# Klingel.net
KiCad netlist of a schematic drawn in EasyEDA
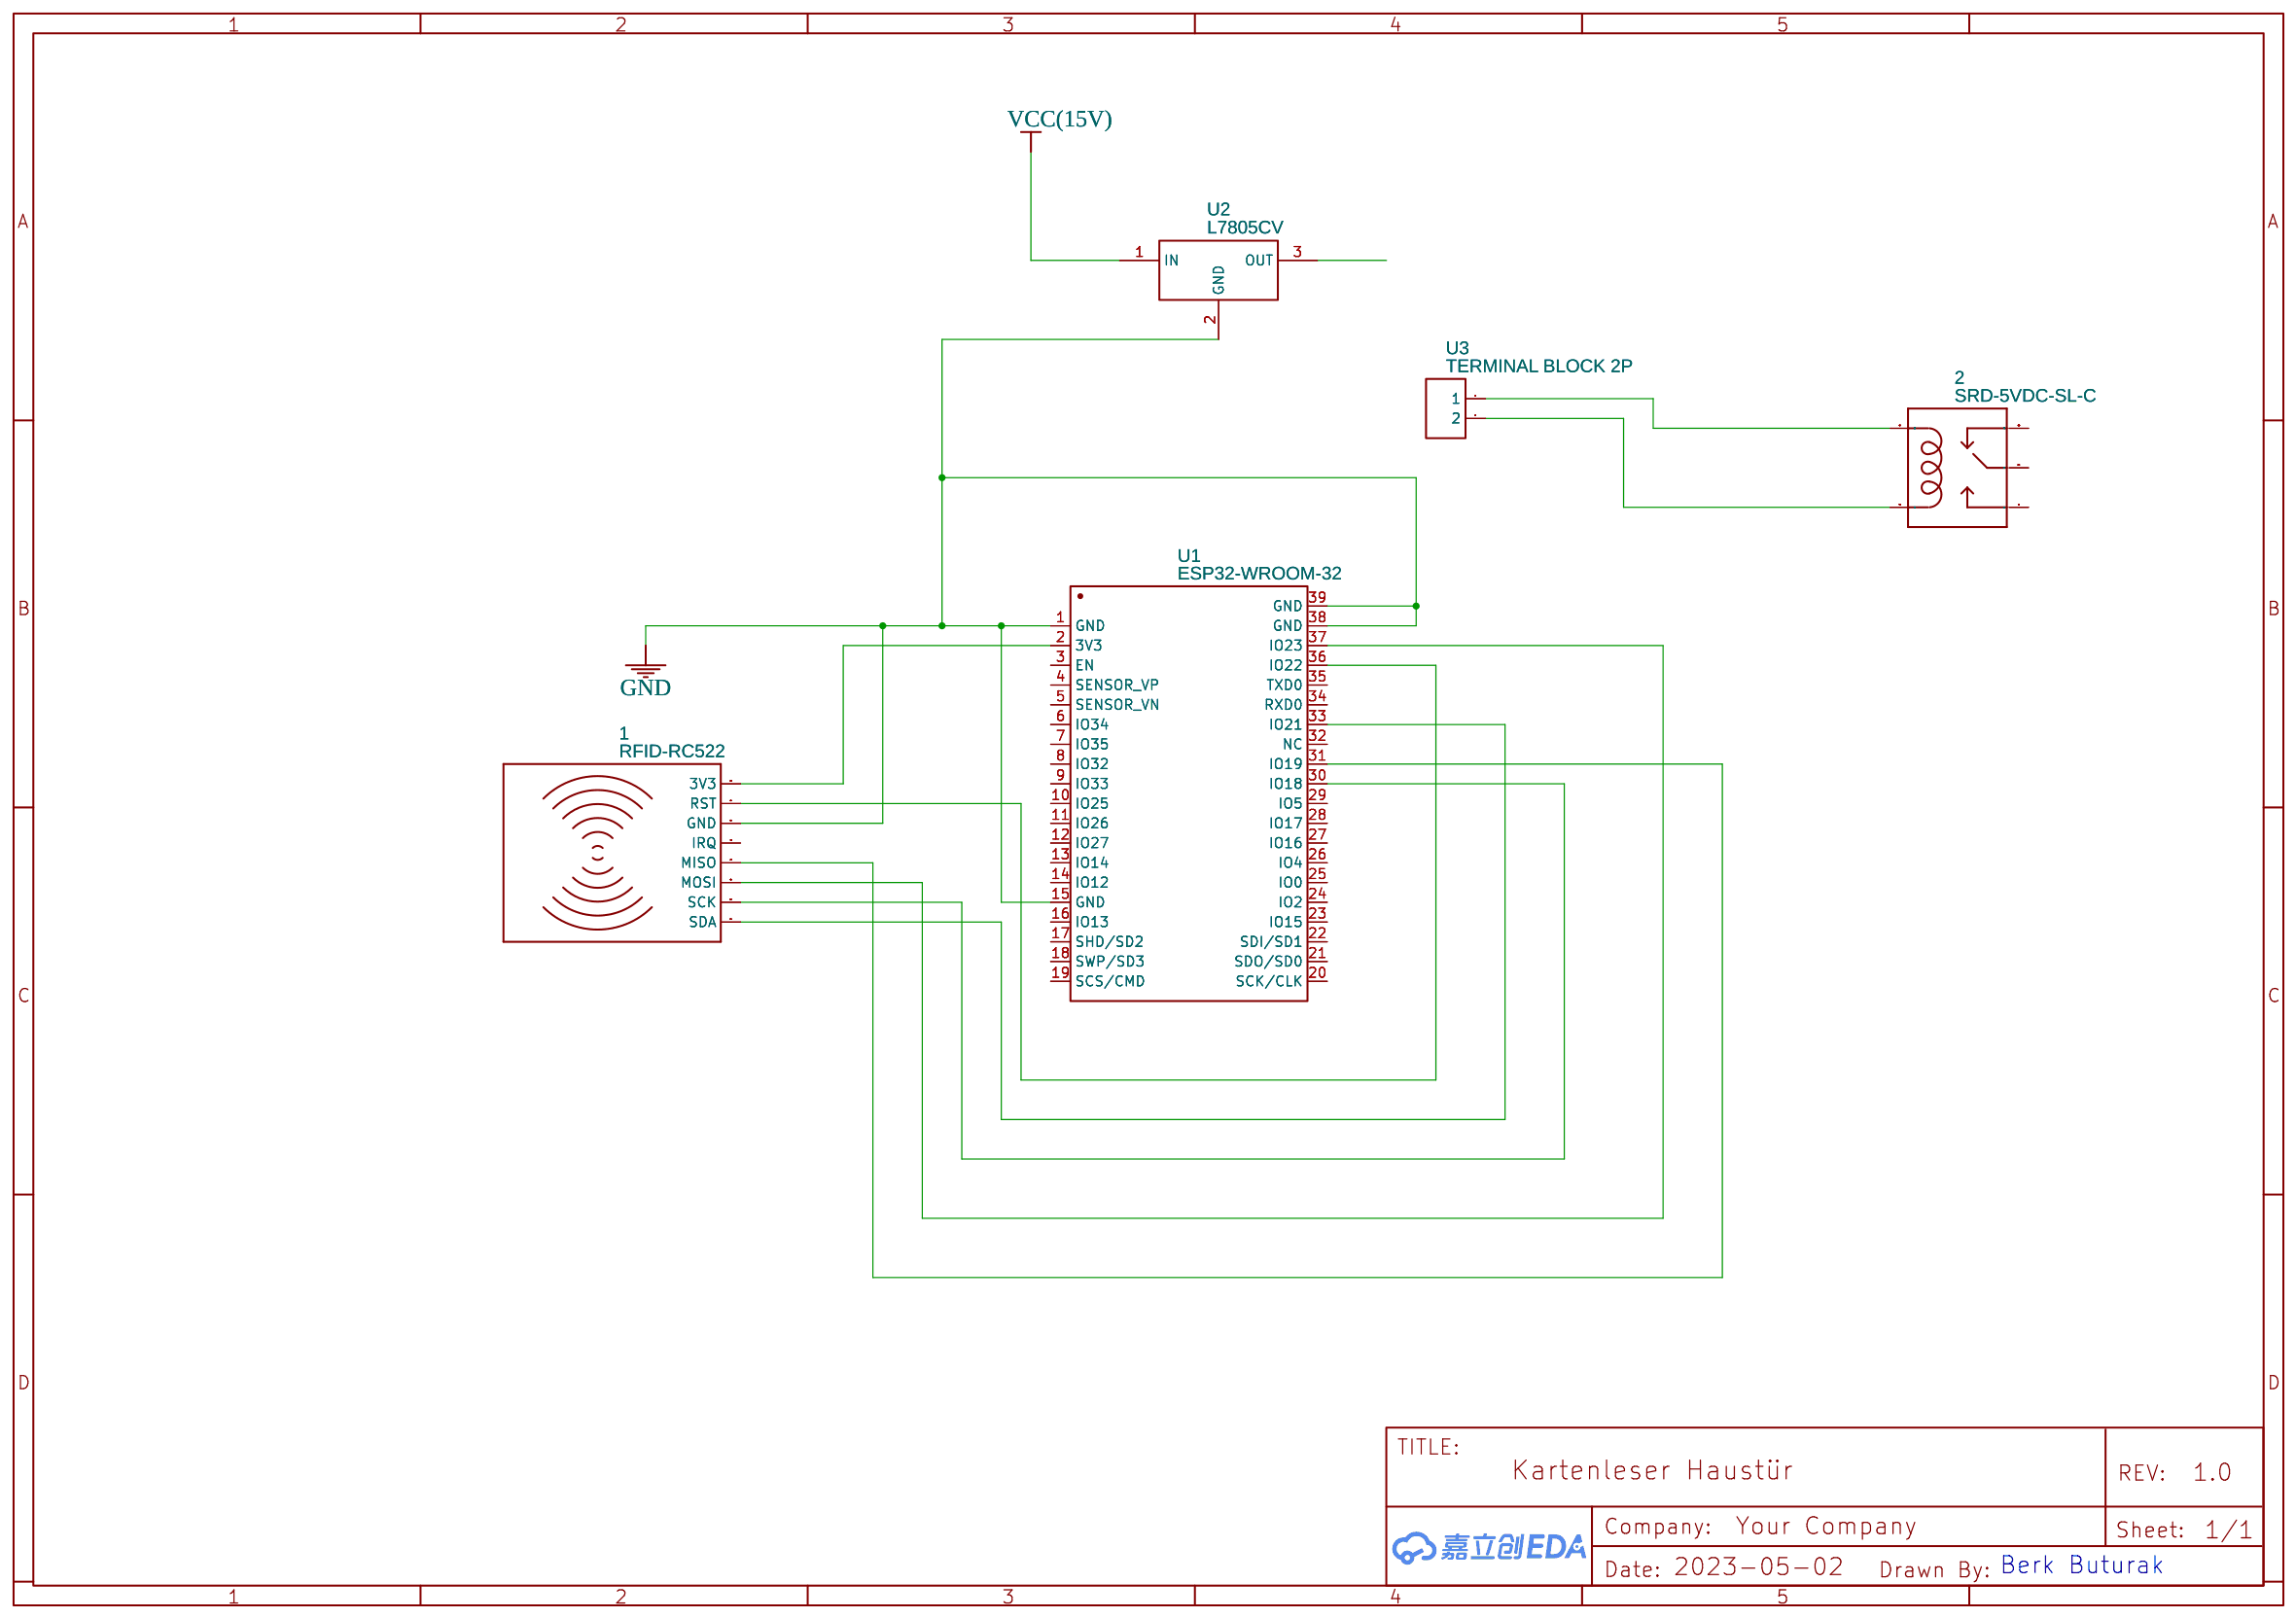
[diagram p0: schematic sheet]

(export (version "E")
  (design (tool "Eeschema 10.0.6"))
  (components
    (comp (ref "1") (value "RFID-RC522") (libsource (lib "") (part "RFID-RC522")))
    (comp (ref "2") (value "SRD-5VDC-SL-C") (libsource (lib "") (part "SRD-5VDC-SL-C")))
    (comp (ref "U1")
      (value "ESP32-WROOM-32")
      (fields
        (field (name "BOM_Manufacturer Part") "ESP32-WROOM-32-N4")
        (field (name "BOM_Supplier Part") "C82899")
      )
      (libsource (lib "") (part "ESP32-WROOM-32"))
    )
    (comp (ref "U2")
      (value "L7805CV")
      (fields (field (name "BOM_Supplier Part") "C111887"))
      (libsource (lib "") (part "L7805CV"))
    )
    (comp (ref "U3") (value "TERMINAL BLOCK 2P") (libsource (lib "") (part "TERMINAL BLOCK 2P")))
  )
  (nets
    (net (code "1") (name "GND") (class "Default")
      (node (ref "1") (pin "GND") (pinfunction "GND_GND") (pintype "bidirectional"))
      (node (ref "U1") (pin "1") (pinfunction "GND_1") (pintype "unspecified"))
      (node (ref "U1") (pin "15") (pinfunction "GND_15") (pintype "unspecified"))
      (node (ref "U1") (pin "38") (pinfunction "GND_38") (pintype "unspecified"))
      (node (ref "U1") (pin "39") (pinfunction "GND_39") (pintype "unspecified"))
      (node (ref "U2") (pin "2") (pinfunction "GND_2") (pintype "passive"))
    )
    (net (code "2") (name "Net-(2-PadCOIL1)") (class "Default")
      (node (ref "2") (pin "COIL1") (pinfunction "COIL1_COIL1") (pintype "bidirectional"))
      (node (ref "U3") (pin "1") (pinfunction "1_1") (pintype "unspecified"))
    )
    (net (code "3") (name "Net-(2-PadCOIL2)") (class "Default")
      (node (ref "2") (pin "COIL2") (pinfunction "COIL2_COIL2") (pintype "bidirectional"))
      (node (ref "U3") (pin "2") (pinfunction "2_2") (pintype "unspecified"))
    )
    (net (code "4") (name "Net-(U1-3V3)") (class "Default")
      (node (ref "1") (pin "3V3") (pinfunction "3V3_3V3") (pintype "bidirectional"))
      (node (ref "U1") (pin "2") (pinfunction "3V3_2") (pintype "unspecified"))
    )
    (net (code "5") (name "Net-(U1-IO18)") (class "Default")
      (node (ref "1") (pin "SCK") (pinfunction "SCK_SCK") (pintype "bidirectional"))
      (node (ref "U1") (pin "30") (pinfunction "IO18_30") (pintype "unspecified"))
    )
    (net (code "6") (name "Net-(U1-IO19)") (class "Default")
      (node (ref "1") (pin "MISO") (pinfunction "MISO_MISO") (pintype "bidirectional"))
      (node (ref "U1") (pin "31") (pinfunction "IO19_31") (pintype "unspecified"))
    )
    (net (code "7") (name "Net-(U1-IO21)") (class "Default")
      (node (ref "1") (pin "SDA") (pinfunction "SDA_SDA") (pintype "bidirectional"))
      (node (ref "U1") (pin "33") (pinfunction "IO21_33") (pintype "unspecified"))
    )
    (net (code "8") (name "Net-(U1-IO22)") (class "Default")
      (node (ref "1") (pin "RST") (pinfunction "RST_RST") (pintype "bidirectional"))
      (node (ref "U1") (pin "36") (pinfunction "IO22_36") (pintype "unspecified"))
    )
    (net (code "9") (name "Net-(U1-IO23)") (class "Default")
      (node (ref "1") (pin "MOSI") (pinfunction "MOSI_MOSI") (pintype "bidirectional"))
      (node (ref "U1") (pin "37") (pinfunction "IO23_37") (pintype "unspecified"))
    )
    (net (code "10") (name "VCC(15V)") (class "Default")
      (node (ref "U2") (pin "1") (pinfunction "IN_1") (pintype "passive"))
    )
    (net (code "11") (name "unconnected-(1-PadIRQ)") (class "Default")
      (node (ref "1") (pin "IRQ") (pinfunction "IRQ_IRQ") (pintype "bidirectional"))
    )
    (net (code "12") (name "unconnected-(2-MAIN-PadCOMMON)") (class "Default")
      (node (ref "2") (pin "COMMON") (pinfunction "MAIN_COMMON") (pintype "bidirectional"))
    )
    (net (code "13") (name "unconnected-(2-NC-PadCLOSED)") (class "Default")
      (node (ref "2") (pin "CLOSED") (pinfunction "NC_CLOSED") (pintype "bidirectional"))
    )
    (net (code "14") (name "unconnected-(2-NO-PadOPEN)") (class "Default")
      (node (ref "2") (pin "OPEN") (pinfunction "NO_OPEN") (pintype "bidirectional"))
    )
    (net (code "15") (name "unconnected-(U1-EN-Pad3)") (class "Default")
      (node (ref "U1") (pin "3") (pinfunction "EN_3") (pintype "unspecified"))
    )
    (net (code "16") (name "unconnected-(U1-IO0-Pad25)") (class "Default")
      (node (ref "U1") (pin "25") (pinfunction "IO0_25") (pintype "unspecified"))
    )
    (net (code "17") (name "unconnected-(U1-IO2-Pad24)") (class "Default")
      (node (ref "U1") (pin "24") (pinfunction "IO2_24") (pintype "unspecified"))
    )
    (net (code "18") (name "unconnected-(U1-IO4-Pad26)") (class "Default")
      (node (ref "U1") (pin "26") (pinfunction "IO4_26") (pintype "unspecified"))
    )
    (net (code "19") (name "unconnected-(U1-IO5-Pad29)") (class "Default")
      (node (ref "U1") (pin "29") (pinfunction "IO5_29") (pintype "unspecified"))
    )
    (net (code "20") (name "unconnected-(U1-IO12-Pad14)") (class "Default")
      (node (ref "U1") (pin "14") (pinfunction "IO12_14") (pintype "unspecified"))
    )
    (net (code "21") (name "unconnected-(U1-IO13-Pad16)") (class "Default")
      (node (ref "U1") (pin "16") (pinfunction "IO13_16") (pintype "unspecified"))
    )
    (net (code "22") (name "unconnected-(U1-IO14-Pad13)") (class "Default")
      (node (ref "U1") (pin "13") (pinfunction "IO14_13") (pintype "unspecified"))
    )
    (net (code "23") (name "unconnected-(U1-IO15-Pad23)") (class "Default")
      (node (ref "U1") (pin "23") (pinfunction "IO15_23") (pintype "unspecified"))
    )
    (net (code "24") (name "unconnected-(U1-IO16-Pad27)") (class "Default")
      (node (ref "U1") (pin "27") (pinfunction "IO16_27") (pintype "unspecified"))
    )
    (net (code "25") (name "unconnected-(U1-IO17-Pad28)") (class "Default")
      (node (ref "U1") (pin "28") (pinfunction "IO17_28") (pintype "unspecified"))
    )
    (net (code "26") (name "unconnected-(U1-IO25-Pad10)") (class "Default")
      (node (ref "U1") (pin "10") (pinfunction "IO25_10") (pintype "unspecified"))
    )
    (net (code "27") (name "unconnected-(U1-IO26-Pad11)") (class "Default")
      (node (ref "U1") (pin "11") (pinfunction "IO26_11") (pintype "unspecified"))
    )
    (net (code "28") (name "unconnected-(U1-IO27-Pad12)") (class "Default")
      (node (ref "U1") (pin "12") (pinfunction "IO27_12") (pintype "unspecified"))
    )
    (net (code "29") (name "unconnected-(U1-IO32-Pad8)") (class "Default")
      (node (ref "U1") (pin "8") (pinfunction "IO32_8") (pintype "unspecified"))
    )
    (net (code "30") (name "unconnected-(U1-IO33-Pad9)") (class "Default")
      (node (ref "U1") (pin "9") (pinfunction "IO33_9") (pintype "unspecified"))
    )
    (net (code "31") (name "unconnected-(U1-IO34-Pad6)") (class "Default")
      (node (ref "U1") (pin "6") (pinfunction "IO34_6") (pintype "unspecified"))
    )
    (net (code "32") (name "unconnected-(U1-IO35-Pad7)") (class "Default")
      (node (ref "U1") (pin "7") (pinfunction "IO35_7") (pintype "unspecified"))
    )
    (net (code "33") (name "unconnected-(U1-NC-Pad32)") (class "Default")
      (node (ref "U1") (pin "32") (pinfunction "NC_32") (pintype "unspecified"))
    )
    (net (code "34") (name "unconnected-(U1-RXD0-Pad34)") (class "Default")
      (node (ref "U1") (pin "34") (pinfunction "RXD0_34") (pintype "unspecified"))
    )
    (net (code "35") (name "unconnected-(U1-SCK{slash}CLK-Pad20)") (class "Default")
      (node (ref "U1") (pin "20") (pinfunction "SCK/CLK_20") (pintype "unspecified"))
    )
    (net (code "36") (name "unconnected-(U1-SCS{slash}CMD-Pad19)") (class "Default")
      (node (ref "U1") (pin "19") (pinfunction "SCS/CMD_19") (pintype "unspecified"))
    )
    (net (code "37") (name "unconnected-(U1-SDI{slash}SD1-Pad22)") (class "Default")
      (node (ref "U1") (pin "22") (pinfunction "SDI/SD1_22") (pintype "unspecified"))
    )
    (net (code "38") (name "unconnected-(U1-SDO{slash}SD0-Pad21)") (class "Default")
      (node (ref "U1") (pin "21") (pinfunction "SDO/SD0_21") (pintype "unspecified"))
    )
    (net (code "39") (name "unconnected-(U1-SENSOR_VN-Pad5)") (class "Default")
      (node (ref "U1") (pin "5") (pinfunction "SENSOR_VN_5") (pintype "unspecified"))
    )
    (net (code "40") (name "unconnected-(U1-SENSOR_VP-Pad4)") (class "Default")
      (node (ref "U1") (pin "4") (pinfunction "SENSOR_VP_4") (pintype "unspecified"))
    )
    (net (code "41") (name "unconnected-(U1-SHD{slash}SD2-Pad17)") (class "Default")
      (node (ref "U1") (pin "17") (pinfunction "SHD/SD2_17") (pintype "unspecified"))
    )
    (net (code "42") (name "unconnected-(U1-SWP{slash}SD3-Pad18)") (class "Default")
      (node (ref "U1") (pin "18") (pinfunction "SWP/SD3_18") (pintype "unspecified"))
    )
    (net (code "43") (name "unconnected-(U1-TXD0-Pad35)") (class "Default")
      (node (ref "U1") (pin "35") (pinfunction "TXD0_35") (pintype "unspecified"))
    )
    (net (code "44") (name "unconnected-(U2-OUT-Pad3)") (class "Default")
      (node (ref "U2") (pin "3") (pinfunction "OUT_3") (pintype "passive"))
    )
  )
)
